# 02_-_EasyEDA.net
KiCad netlist of a schematic drawn in EasyEDA
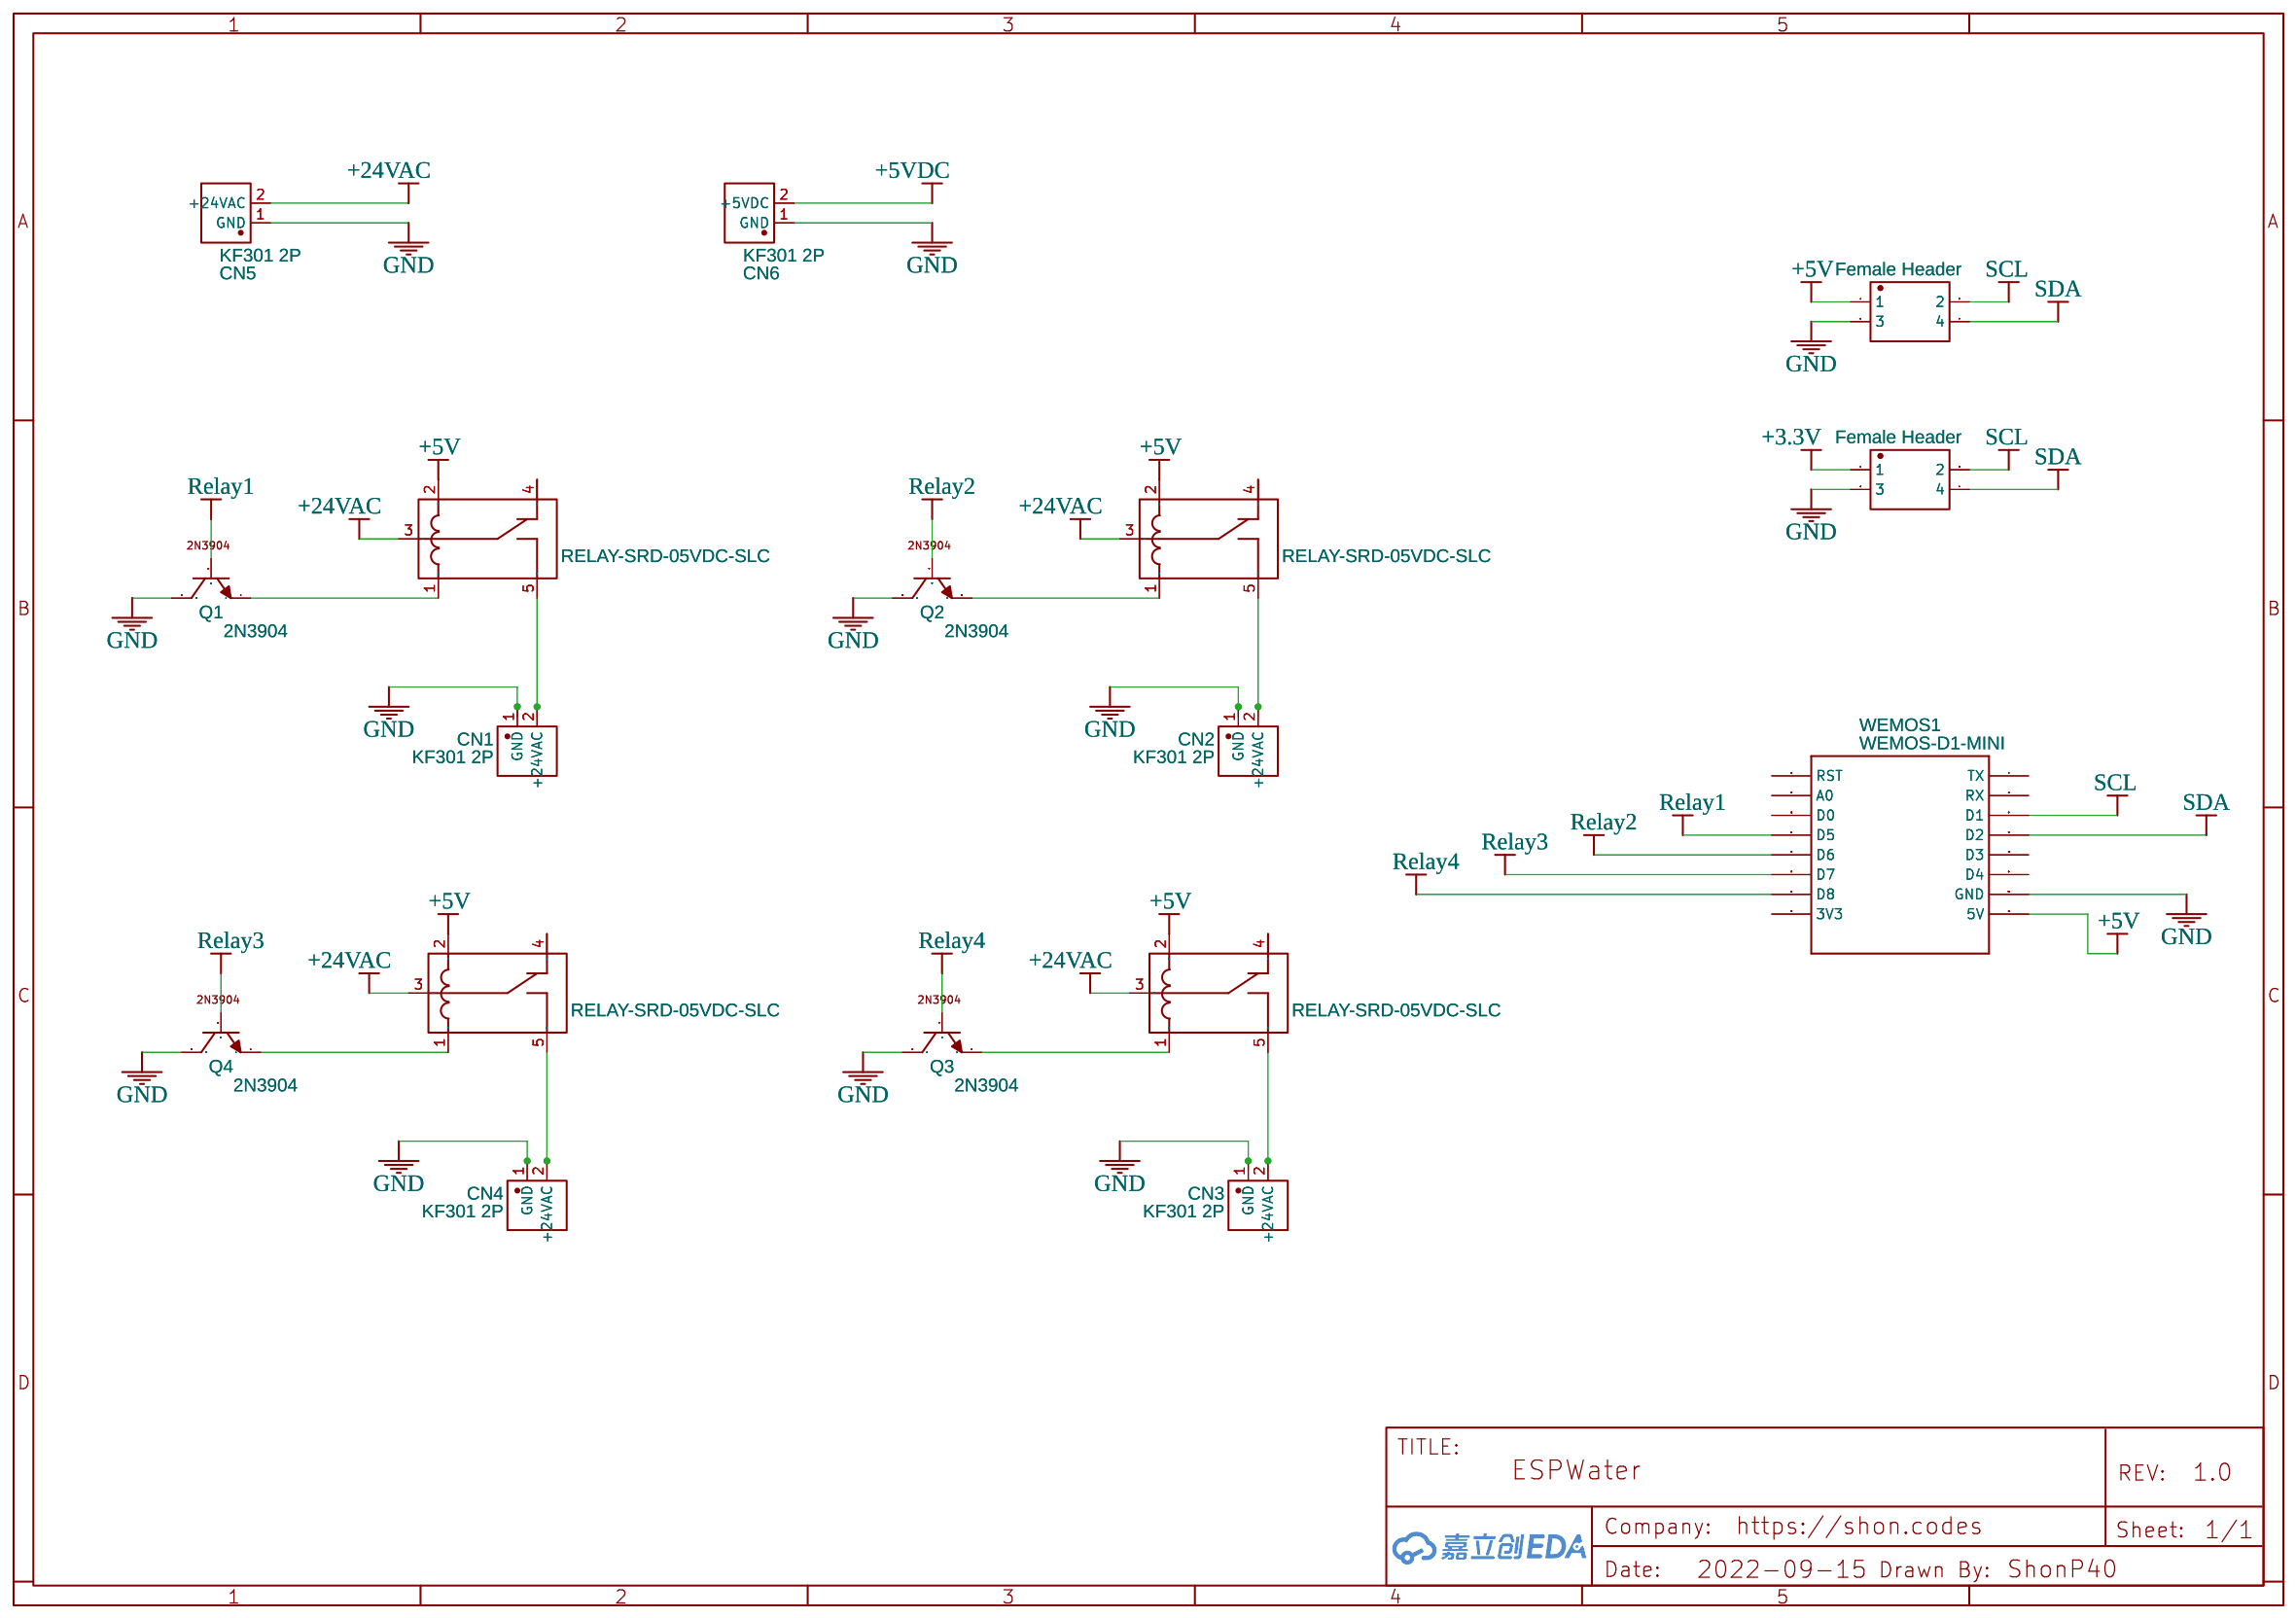
[diagram p0: schematic sheet]

(export (version "E")
  (design (tool "Eeschema 10.0.6"))
  (components
    (comp (ref "1") (value "RELAY-SRD-05VDC-SLC") (libsource (lib "") (part "RELAY-SRD-05VDC-SLC")))
    (comp (ref "2") (value "RELAY-SRD-05VDC-SLC") (libsource (lib "") (part "RELAY-SRD-05VDC-SLC")))
    (comp (ref "3") (value "RELAY-SRD-05VDC-SLC") (libsource (lib "") (part "RELAY-SRD-05VDC-SLC")))
    (comp (ref "4") (value "RELAY-SRD-05VDC-SLC") (libsource (lib "") (part "RELAY-SRD-05VDC-SLC")))
    (comp (ref "CN1")
      (value "KF301 2P")
      (fields
        (field (name "BOM_Manufacturer Part") "JL2EDGRC-50803G01")
        (field (name "BOM_Supplier Part") "C387830")
      )
      (libsource (lib "") (part "KF301 2P_1"))
    )
    (comp (ref "CN2")
      (value "KF301 2P")
      (fields
        (field (name "BOM_Manufacturer Part") "JL2EDGRC-50803G01")
        (field (name "BOM_Supplier Part") "C387830")
      )
      (libsource (lib "") (part "KF301 2P_1"))
    )
    (comp (ref "CN3")
      (value "KF301 2P")
      (fields
        (field (name "BOM_Manufacturer Part") "JL2EDGRC-50803G01")
        (field (name "BOM_Supplier Part") "C387830")
      )
      (libsource (lib "") (part "KF301 2P_1"))
    )
    (comp (ref "CN4")
      (value "KF301 2P")
      (fields
        (field (name "BOM_Manufacturer Part") "JL2EDGRC-50803G01")
        (field (name "BOM_Supplier Part") "C387830")
      )
      (libsource (lib "") (part "KF301 2P_1"))
    )
    (comp (ref "CN5")
      (value "KF301 2P")
      (fields
        (field (name "BOM_Manufacturer Part") "JL2EDGRC-50803G01")
        (field (name "BOM_Supplier Part") "C387830")
      )
      (libsource (lib "") (part "KF301 2P"))
    )
    (comp (ref "CN6")
      (value "KF301 2P")
      (fields
        (field (name "BOM_Manufacturer Part") "JL2EDGRC-50803G01")
        (field (name "BOM_Supplier Part") "C387830")
      )
      (libsource (lib "") (part "KF301 2P_2"))
    )
    (comp (ref "H1")
      (value "Female Header")
      (fields
        (field (name "BOM_Manufacturer Part") "DS1023-2*2SF11")
        (field (name "BOM_Supplier Part") "C92273")
      )
      (libsource (lib "") (part "Header-Female-2.54_2x2"))
    )
    (comp (ref "H2")
      (value "Female Header")
      (fields
        (field (name "BOM_Manufacturer Part") "DS1023-2*2SF11")
        (field (name "BOM_Supplier Part") "C92273")
      )
      (libsource (lib "") (part "Header-Female-2.54_2x2"))
    )
    (comp (ref "Q1") (value "2N3904") (libsource (lib "") (part "2N3904")))
    (comp (ref "Q2") (value "2N3904") (libsource (lib "") (part "2N3904")))
    (comp (ref "Q3") (value "2N3904") (libsource (lib "") (part "2N3904")))
    (comp (ref "Q4") (value "2N3904") (libsource (lib "") (part "2N3904")))
    (comp (ref "WEMOS1") (value "WEMOS-D1-MINI") (libsource (lib "") (part "WEMOS-D1-MINI")))
  )
  (nets
    (net (code "1") (name "+3.3V") (class "Default")
      (node (ref "H2") (pin "1") (pinfunction "1_1") (pintype "unspecified"))
    )
    (net (code "2") (name "+5V") (class "Default")
      (node (ref "1") (pin "2") (pinfunction "2_2") (pintype "unspecified"))
      (node (ref "2") (pin "2") (pinfunction "2_2") (pintype "unspecified"))
      (node (ref "3") (pin "2") (pinfunction "2_2") (pintype "unspecified"))
      (node (ref "4") (pin "2") (pinfunction "2_2") (pintype "unspecified"))
      (node (ref "H1") (pin "1") (pinfunction "1_1") (pintype "unspecified"))
      (node (ref "WEMOS1") (pin "5V") (pinfunction "5V_5V") (pintype "unspecified"))
    )
    (net (code "3") (name "+5VDC") (class "Default")
      (node (ref "CN6") (pin "2") (pinfunction "+5VDC_2") (pintype "unspecified"))
    )
    (net (code "4") (name "+24VAC") (class "Default")
      (node (ref "1") (pin "3") (pinfunction "3_3") (pintype "unspecified"))
      (node (ref "2") (pin "3") (pinfunction "3_3") (pintype "unspecified"))
      (node (ref "3") (pin "3") (pinfunction "3_3") (pintype "unspecified"))
      (node (ref "4") (pin "3") (pinfunction "3_3") (pintype "unspecified"))
      (node (ref "CN5") (pin "2") (pinfunction "+24VAC_2") (pintype "unspecified"))
    )
    (net (code "5") (name "GND") (class "Default")
      (node (ref "CN1") (pin "1") (pinfunction "GND_1") (pintype "unspecified"))
      (node (ref "CN2") (pin "1") (pinfunction "GND_1") (pintype "unspecified"))
      (node (ref "CN3") (pin "1") (pinfunction "GND_1") (pintype "unspecified"))
      (node (ref "CN4") (pin "1") (pinfunction "GND_1") (pintype "unspecified"))
      (node (ref "CN5") (pin "1") (pinfunction "GND_1") (pintype "unspecified"))
      (node (ref "CN6") (pin "1") (pinfunction "GND_1") (pintype "unspecified"))
      (node (ref "H1") (pin "3") (pinfunction "3_3") (pintype "unspecified"))
      (node (ref "H2") (pin "3") (pinfunction "3_3") (pintype "unspecified"))
      (node (ref "Q1") (pin "3") (pinfunction "C_3") (pintype "unspecified"))
      (node (ref "Q2") (pin "3") (pinfunction "C_3") (pintype "unspecified"))
      (node (ref "Q3") (pin "3") (pinfunction "C_3") (pintype "unspecified"))
      (node (ref "Q4") (pin "3") (pinfunction "C_3") (pintype "unspecified"))
      (node (ref "WEMOS1") (pin "GND") (pinfunction "GND_GND") (pintype "unspecified"))
    )
    (net (code "6") (name "Net-(CN1-+24VAC)") (class "Default")
      (node (ref "1") (pin "5") (pinfunction "5_5") (pintype "unspecified"))
      (node (ref "CN1") (pin "2") (pinfunction "+24VAC_2") (pintype "unspecified"))
    )
    (net (code "7") (name "Net-(CN2-+24VAC)") (class "Default")
      (node (ref "2") (pin "5") (pinfunction "5_5") (pintype "unspecified"))
      (node (ref "CN2") (pin "2") (pinfunction "+24VAC_2") (pintype "unspecified"))
    )
    (net (code "8") (name "Net-(CN3-+24VAC)") (class "Default")
      (node (ref "3") (pin "5") (pinfunction "5_5") (pintype "unspecified"))
      (node (ref "CN3") (pin "2") (pinfunction "+24VAC_2") (pintype "unspecified"))
    )
    (net (code "9") (name "Net-(CN4-+24VAC)") (class "Default")
      (node (ref "4") (pin "5") (pinfunction "5_5") (pintype "unspecified"))
      (node (ref "CN4") (pin "2") (pinfunction "+24VAC_2") (pintype "unspecified"))
    )
    (net (code "10") (name "Net-(Q1-E)") (class "Default")
      (node (ref "1") (pin "1") (pinfunction "1_1") (pintype "unspecified"))
      (node (ref "Q1") (pin "1") (pinfunction "E_1") (pintype "unspecified"))
    )
    (net (code "11") (name "Net-(Q2-E)") (class "Default")
      (node (ref "2") (pin "1") (pinfunction "1_1") (pintype "unspecified"))
      (node (ref "Q2") (pin "1") (pinfunction "E_1") (pintype "unspecified"))
    )
    (net (code "12") (name "Net-(Q3-E)") (class "Default")
      (node (ref "3") (pin "1") (pinfunction "1_1") (pintype "unspecified"))
      (node (ref "Q3") (pin "1") (pinfunction "E_1") (pintype "unspecified"))
    )
    (net (code "13") (name "Net-(Q4-E)") (class "Default")
      (node (ref "4") (pin "1") (pinfunction "1_1") (pintype "unspecified"))
      (node (ref "Q4") (pin "1") (pinfunction "E_1") (pintype "unspecified"))
    )
    (net (code "14") (name "Relay1") (class "Default")
      (node (ref "Q1") (pin "2") (pinfunction "B_2") (pintype "unspecified"))
      (node (ref "WEMOS1") (pin "D5") (pinfunction "D5_D5") (pintype "unspecified"))
    )
    (net (code "15") (name "Relay2") (class "Default")
      (node (ref "Q2") (pin "2") (pinfunction "B_2") (pintype "unspecified"))
      (node (ref "WEMOS1") (pin "D6") (pinfunction "D6_D6") (pintype "unspecified"))
    )
    (net (code "16") (name "Relay3") (class "Default")
      (node (ref "Q4") (pin "2") (pinfunction "B_2") (pintype "unspecified"))
      (node (ref "WEMOS1") (pin "D7") (pinfunction "D7_D7") (pintype "unspecified"))
    )
    (net (code "17") (name "Relay4") (class "Default")
      (node (ref "Q3") (pin "2") (pinfunction "B_2") (pintype "unspecified"))
      (node (ref "WEMOS1") (pin "D8") (pinfunction "D8_D8") (pintype "unspecified"))
    )
    (net (code "18") (name "SCL") (class "Default")
      (node (ref "H1") (pin "2") (pinfunction "2_2") (pintype "unspecified"))
      (node (ref "H2") (pin "2") (pinfunction "2_2") (pintype "unspecified"))
      (node (ref "WEMOS1") (pin "D1") (pinfunction "D1_D1") (pintype "unspecified"))
    )
    (net (code "19") (name "SDA") (class "Default")
      (node (ref "H1") (pin "4") (pinfunction "4_4") (pintype "unspecified"))
      (node (ref "H2") (pin "4") (pinfunction "4_4") (pintype "unspecified"))
      (node (ref "WEMOS1") (pin "D2") (pinfunction "D2_D2") (pintype "unspecified"))
    )
    (net (code "20") (name "unconnected-(1-Pad4)") (class "Default")
      (node (ref "1") (pin "4") (pinfunction "4_4") (pintype "unspecified"))
    )
    (net (code "21") (name "unconnected-(2-Pad4)") (class "Default")
      (node (ref "2") (pin "4") (pinfunction "4_4") (pintype "unspecified"))
    )
    (net (code "22") (name "unconnected-(3-Pad4)") (class "Default")
      (node (ref "3") (pin "4") (pinfunction "4_4") (pintype "unspecified"))
    )
    (net (code "23") (name "unconnected-(4-Pad4)") (class "Default")
      (node (ref "4") (pin "4") (pinfunction "4_4") (pintype "unspecified"))
    )
    (net (code "24") (name "unconnected-(WEMOS1-Pad3V3)") (class "Default")
      (node (ref "WEMOS1") (pin "3V3") (pinfunction "3V3_3V3") (pintype "unspecified"))
    )
    (net (code "25") (name "unconnected-(WEMOS1-PadA0)") (class "Default")
      (node (ref "WEMOS1") (pin "A0") (pinfunction "A0_A0") (pintype "unspecified"))
    )
    (net (code "26") (name "unconnected-(WEMOS1-PadD0)") (class "Default")
      (node (ref "WEMOS1") (pin "D0") (pinfunction "D0_D0") (pintype "unspecified"))
    )
    (net (code "27") (name "unconnected-(WEMOS1-PadD3)") (class "Default")
      (node (ref "WEMOS1") (pin "D3") (pinfunction "D3_D3") (pintype "unspecified"))
    )
    (net (code "28") (name "unconnected-(WEMOS1-PadD4)") (class "Default")
      (node (ref "WEMOS1") (pin "D4") (pinfunction "D4_D4") (pintype "unspecified"))
    )
    (net (code "29") (name "unconnected-(WEMOS1-PadRST)") (class "Default")
      (node (ref "WEMOS1") (pin "RST") (pinfunction "RST_RST") (pintype "unspecified"))
    )
    (net (code "30") (name "unconnected-(WEMOS1-PadRX)") (class "Default")
      (node (ref "WEMOS1") (pin "RX") (pinfunction "RX_RX") (pintype "unspecified"))
    )
    (net (code "31") (name "unconnected-(WEMOS1-PadTX)") (class "Default")
      (node (ref "WEMOS1") (pin "TX") (pinfunction "TX_TX") (pintype "unspecified"))
    )
  )
)
